# Main.net
KiCad netlist of a schematic drawn in Altium Designer
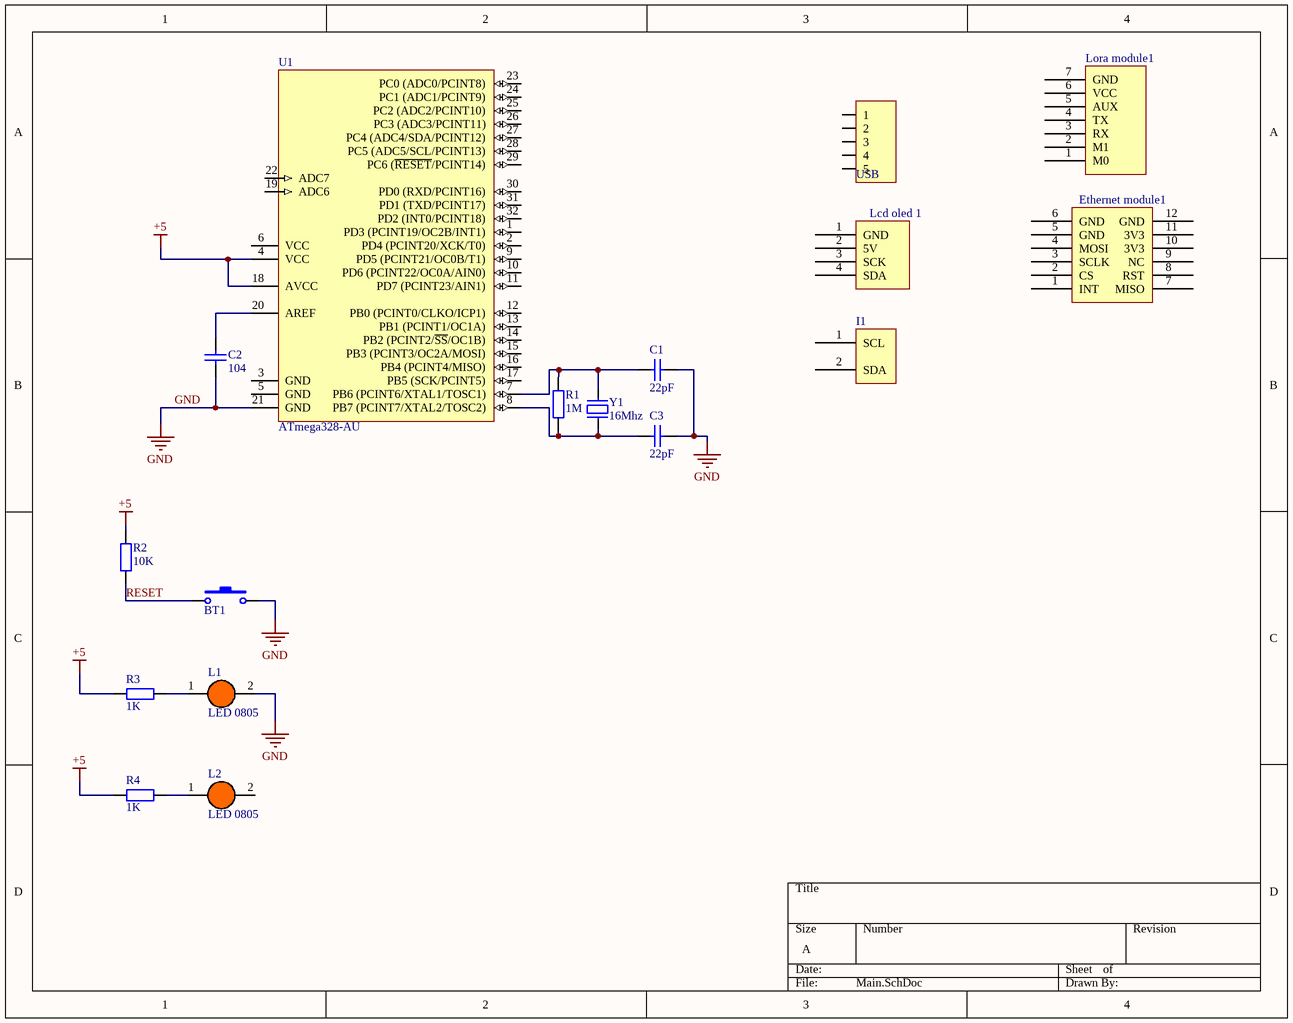
[diagram p0: Main.SchDoc]

(export (version "E")
  (design (tool "Eeschema 10.0.6"))
  (components
    (comp (ref "BT1")
      (value "Nut Nhan 2 Chan SMD 3x6x2.5")
      (footprint "Nut Nhan 2 Chan SMD 3x6x2.5")
      (libsource (lib "Altium_Lib_by_KhueNguyenCreator") (part "Nut Nhan 2 Chan SMD 3x6x2.5"))
    )
    (comp (ref "C1")
      (value "22pF")
      (footprint "tu 0603")
      (description "Dán")
      (libsource (lib "Altium_Lib_by_KhueNguyenCreator") (part "Tu 0603 22pF 50V 10%"))
    )
    (comp (ref "C2")
      (value "104")
      (footprint "tu 0603")
      (description "Dán")
      (libsource (lib "Altium_Lib_by_KhueNguyenCreator") (part "Tu 0603 104 50V 10%"))
    )
    (comp (ref "C3")
      (value "22pF")
      (footprint "tu 0603")
      (description "Dán")
      (libsource (lib "Altium_Lib_by_KhueNguyenCreator") (part "Tu 0603 22pF 50V 10%"))
    )
    (comp (ref "Ethernet module1")
      (value "Ethernet module")
      (footprint "Ethernet module - duplicate")
      (libsource (lib "SPI") (part "Ethernet module"))
    )
    (comp (ref "I1") (value "I2C") (footprint "CON2") (libsource (lib "Schlib2") (part "I2C")))
    (comp (ref "JP1")
      (value "USB")
      (footprint "JP 1x5 CT")
      (description "Cắm")
      (libsource (lib "Altium_Lib_by_KhueNguyenCreator") (part "JP 1x5 2.54 Cai Thang"))
    )
    (comp (ref "L1")
      (value "LED 0805")
      (footprint "LED-0805-Orange")
      (description "Dán")
      (libsource (lib "Altium_Lib_by_KhueNguyenCreator") (part "LED 0805 Cam"))
    )
    (comp (ref "L2")
      (value "LED 0805")
      (footprint "LED-0805-Orange")
      (description "Dán")
      (libsource (lib "Altium_Lib_by_KhueNguyenCreator") (part "LED 0805 Cam"))
    )
    (comp (ref "Lcd oled 1")
      (value "Lcd oled 1306 module")
      (footprint "LCD 1306 - duplicate")
      (libsource (lib "SPI") (part "Lcd oled 1306 module"))
    )
    (comp (ref "Lora module1")
      (value "Lora module")
      (footprint "LORA")
      (libsource (lib "SPI") (part "Lora module"))
    )
    (comp (ref "R1")
      (value "1M")
      (footprint "tro smd 0805")
      (description "Dán")
      (libsource (lib "Altium_Lib_by_KhueNguyenCreator") (part "Tro 0805 5% 1M"))
    )
    (comp (ref "R2")
      (value "10K")
      (footprint "tro smd 0603")
      (description "Dán")
      (libsource (lib "Altium_Lib_by_KhueNguyenCreator") (part "Tro 0603 5% 220R"))
    )
    (comp (ref "R3")
      (value "1K")
      (footprint "tro smd 0603")
      (description "Dán")
      (libsource (lib "Altium_Lib_by_KhueNguyenCreator") (part "Tro 0603 5% 220R"))
    )
    (comp (ref "R4")
      (value "1K")
      (footprint "tro smd 0603")
      (description "Dán")
      (libsource (lib "Altium_Lib_by_KhueNguyenCreator") (part "Tro 0603 5% 220R"))
    )
    (comp (ref "U1")
      (value "ATmega328-AU")
      (footprint "TQFP32")
      (fields (field (name "PUBLISHER") "Altium Limited"))
      (libsource (lib "LIBRARY1") (part "ATmega328-AU"))
    )
    (comp (ref "Y1")
      (value "16Mhz")
      (footprint "Thach Anh 2 chan SMD")
      (description "Crystal For all Crystal 2pin.")
      (libsource (lib "Altium_Lib_by_KhueNguyenCreator") (part "Thach Anh 2 chan SMD"))
    )
  )
  (nets
    (net (code "1") (name "+5") (class "Default")
      (node (ref "R2") (pin "2") (pinfunction "2_2") (pintype "passive"))
      (node (ref "R3") (pin "1") (pinfunction "1_1") (pintype "passive"))
      (node (ref "R4") (pin "1") (pinfunction "1_1") (pintype "passive"))
      (node (ref "U1") (pin "18") (pinfunction "AVCC_18") (pintype "power_in"))
      (node (ref "U1") (pin "4") (pinfunction "VCC_4") (pintype "power_in"))
    )
    (net (code "2") (name "/RESET") (class "Default")
      (node (ref "BT1") (pin "1") (pinfunction "1_1") (pintype "passive"))
      (node (ref "R2") (pin "1") (pinfunction "1_1") (pintype "passive"))
    )
    (net (code "3") (name "GND") (class "Default")
      (node (ref "BT1") (pin "2") (pinfunction "2_2") (pintype "passive"))
      (node (ref "C1") (pin "2") (pinfunction "2_2") (pintype "passive"))
      (node (ref "C2") (pin "2") (pinfunction "2_2") (pintype "passive"))
      (node (ref "C3") (pin "2") (pinfunction "2_2") (pintype "passive"))
      (node (ref "L1") (pin "2") (pinfunction "K_2") (pintype "passive"))
      (node (ref "U1") (pin "21") (pinfunction "GND_21") (pintype "power_in"))
    )
    (net (code "4") (name "Net-(L1-A)") (class "Default")
      (node (ref "L1") (pin "1") (pinfunction "A_1") (pintype "passive"))
      (node (ref "R3") (pin "2") (pinfunction "2_2") (pintype "passive"))
    )
    (net (code "5") (name "Net-(L2-A)") (class "Default")
      (node (ref "L2") (pin "1") (pinfunction "A_1") (pintype "passive"))
      (node (ref "R4") (pin "2") (pinfunction "2_2") (pintype "passive"))
    )
    (net (code "6") (name "Net-(U1-AREF)") (class "Default")
      (node (ref "C2") (pin "1") (pinfunction "1_1") (pintype "passive"))
      (node (ref "U1") (pin "20") (pinfunction "AREF_20") (pintype "passive"))
    )
    (net (code "7") (name "Net-(U1-PB6_(PCINT6{slash}XTAL1{slash}TOSC1))") (class "Default")
      (node (ref "C1") (pin "1") (pinfunction "1_1") (pintype "passive"))
      (node (ref "U1") (pin "7") (pinfunction "PB6_(PCINT6/XTAL1/TOSC1)_7") (pintype "bidirectional"))
      (node (ref "Y1") (pin "1") (pinfunction "1_1") (pintype "passive"))
    )
    (net (code "8") (name "Net-(U1-PB7_(PCINT7{slash}XTAL2{slash}TOSC2))") (class "Default")
      (node (ref "C3") (pin "1") (pinfunction "1_1") (pintype "passive"))
      (node (ref "R1") (pin "2") (pinfunction "2_2") (pintype "passive"))
      (node (ref "U1") (pin "8") (pinfunction "PB7_(PCINT7/XTAL2/TOSC2)_8") (pintype "bidirectional"))
      (node (ref "Y1") (pin "2") (pinfunction "2_2") (pintype "passive"))
    )
    (net (code "9") (name "unconnected-(Ethernet module1-3V3-Pad10)") (class "Default")
      (node (ref "Ethernet module1") (pin "10") (pinfunction "3V3_10") (pintype "passive"))
    )
    (net (code "10") (name "unconnected-(Ethernet module1-3V3-Pad11)") (class "Default")
      (node (ref "Ethernet module1") (pin "11") (pinfunction "3V3_11") (pintype "passive"))
    )
    (net (code "11") (name "unconnected-(Ethernet module1-CS-Pad2)") (class "Default")
      (node (ref "Ethernet module1") (pin "2") (pinfunction "CS_2") (pintype "passive"))
    )
    (net (code "12") (name "unconnected-(Ethernet module1-GND-Pad5)") (class "Default")
      (node (ref "Ethernet module1") (pin "5") (pinfunction "GND_5") (pintype "passive"))
    )
    (net (code "13") (name "unconnected-(Ethernet module1-GND-Pad6)") (class "Default")
      (node (ref "Ethernet module1") (pin "6") (pinfunction "GND_6") (pintype "passive"))
    )
    (net (code "14") (name "unconnected-(Ethernet module1-GND-Pad12)") (class "Default")
      (node (ref "Ethernet module1") (pin "12") (pinfunction "GND_12") (pintype "passive"))
    )
    (net (code "15") (name "unconnected-(Ethernet module1-INT-Pad1)") (class "Default")
      (node (ref "Ethernet module1") (pin "1") (pinfunction "INT_1") (pintype "passive"))
    )
    (net (code "16") (name "unconnected-(Ethernet module1-MISO-Pad7)") (class "Default")
      (node (ref "Ethernet module1") (pin "7") (pinfunction "MISO_7") (pintype "passive"))
    )
    (net (code "17") (name "unconnected-(Ethernet module1-MOSI-Pad4)") (class "Default")
      (node (ref "Ethernet module1") (pin "4") (pinfunction "MOSI_4") (pintype "passive"))
    )
    (net (code "18") (name "unconnected-(Ethernet module1-NC-Pad9)") (class "Default")
      (node (ref "Ethernet module1") (pin "9") (pinfunction "NC_9") (pintype "passive"))
    )
    (net (code "19") (name "unconnected-(Ethernet module1-RST-Pad8)") (class "Default")
      (node (ref "Ethernet module1") (pin "8") (pinfunction "RST_8") (pintype "passive"))
    )
    (net (code "20") (name "unconnected-(Ethernet module1-SCLK-Pad3)") (class "Default")
      (node (ref "Ethernet module1") (pin "3") (pinfunction "SCLK_3") (pintype "passive"))
    )
    (net (code "21") (name "unconnected-(I1-SCL-Pad1)") (class "Default")
      (node (ref "I1") (pin "1") (pinfunction "SCL_1") (pintype "passive"))
    )
    (net (code "22") (name "unconnected-(I1-SDA-Pad2)") (class "Default")
      (node (ref "I1") (pin "2") (pinfunction "SDA_2") (pintype "passive"))
    )
    (net (code "23") (name "unconnected-(JP1-Pad1)") (class "Default")
      (node (ref "JP1") (pin "1") (pinfunction "1_1") (pintype "passive"))
    )
    (net (code "24") (name "unconnected-(JP1-Pad2)") (class "Default")
      (node (ref "JP1") (pin "2") (pinfunction "2_2") (pintype "passive"))
    )
    (net (code "25") (name "unconnected-(JP1-Pad3)") (class "Default")
      (node (ref "JP1") (pin "3") (pinfunction "3_3") (pintype "passive"))
    )
    (net (code "26") (name "unconnected-(JP1-Pad4)") (class "Default")
      (node (ref "JP1") (pin "4") (pinfunction "4_4") (pintype "passive"))
    )
    (net (code "27") (name "unconnected-(JP1-Pad5)") (class "Default")
      (node (ref "JP1") (pin "5") (pinfunction "5_5") (pintype "passive"))
    )
    (net (code "28") (name "unconnected-(L2-K-Pad2)") (class "Default")
      (node (ref "L2") (pin "2") (pinfunction "K_2") (pintype "passive"))
    )
    (net (code "29") (name "unconnected-(Lcd oled 1-5V-Pad2)") (class "Default")
      (node (ref "Lcd oled 1") (pin "2") (pinfunction "5V_2") (pintype "passive"))
    )
    (net (code "30") (name "unconnected-(Lcd oled 1-GND-Pad1)") (class "Default")
      (node (ref "Lcd oled 1") (pin "1") (pinfunction "GND_1") (pintype "passive"))
    )
    (net (code "31") (name "unconnected-(Lcd oled 1-SCK-Pad3)") (class "Default")
      (node (ref "Lcd oled 1") (pin "3") (pinfunction "SCK_3") (pintype "passive"))
    )
    (net (code "32") (name "unconnected-(Lcd oled 1-SDA-Pad4)") (class "Default")
      (node (ref "Lcd oled 1") (pin "4") (pinfunction "SDA_4") (pintype "passive"))
    )
    (net (code "33") (name "unconnected-(Lora module1-AUX-Pad5)") (class "Default")
      (node (ref "Lora module1") (pin "5") (pinfunction "AUX_5") (pintype "passive"))
    )
    (net (code "34") (name "unconnected-(Lora module1-GND-Pad7)") (class "Default")
      (node (ref "Lora module1") (pin "7") (pinfunction "GND_7") (pintype "power_in"))
    )
    (net (code "35") (name "unconnected-(Lora module1-M0-Pad1)") (class "Default")
      (node (ref "Lora module1") (pin "1") (pinfunction "M0_1") (pintype "passive"))
    )
    (net (code "36") (name "unconnected-(Lora module1-M1-Pad2)") (class "Default")
      (node (ref "Lora module1") (pin "2") (pinfunction "M1_2") (pintype "passive"))
    )
    (net (code "37") (name "unconnected-(Lora module1-RX-Pad3)") (class "Default")
      (node (ref "Lora module1") (pin "3") (pinfunction "RX_3") (pintype "passive"))
    )
    (net (code "38") (name "unconnected-(Lora module1-TX-Pad4)") (class "Default")
      (node (ref "Lora module1") (pin "4") (pinfunction "TX_4") (pintype "passive"))
    )
    (net (code "39") (name "unconnected-(Lora module1-VCC-Pad6)") (class "Default")
      (node (ref "Lora module1") (pin "6") (pinfunction "VCC_6") (pintype "power_in"))
    )
    (net (code "40") (name "unconnected-(R1-Pad1)") (class "Default")
      (node (ref "R1") (pin "1") (pinfunction "1_1") (pintype "passive"))
    )
    (net (code "41") (name "unconnected-(U1-ADC6-Pad19)") (class "Default")
      (node (ref "U1") (pin "19") (pinfunction "ADC6_19") (pintype "input"))
    )
    (net (code "42") (name "unconnected-(U1-ADC7-Pad22)") (class "Default")
      (node (ref "U1") (pin "22") (pinfunction "ADC7_22") (pintype "input"))
    )
    (net (code "43") (name "unconnected-(U1-GND-Pad3)") (class "Default")
      (node (ref "U1") (pin "3") (pinfunction "GND_3") (pintype "power_in"))
    )
    (net (code "44") (name "unconnected-(U1-GND-Pad5)") (class "Default")
      (node (ref "U1") (pin "5") (pinfunction "GND_5") (pintype "power_in"))
    )
    (net (code "45") (name "unconnected-(U1-PB0_(PCINT0{slash}CLKO{slash}ICP1)-Pad12)") (class "Default")
      (node (ref "U1") (pin "12") (pinfunction "PB0_(PCINT0/CLKO/ICP1)_12") (pintype "bidirectional"))
    )
    (net (code "46") (name "unconnected-(U1-PB1_(PCINT1{slash}OC1A)-Pad13)") (class "Default")
      (node (ref "U1") (pin "13") (pinfunction "PB1_(PCINT1/OC1A)_13") (pintype "bidirectional"))
    )
    (net (code "47") (name "unconnected-(U1-PB2_(PCINT2{slash}~{SS}{slash}OC1B)-Pad14)") (class "Default")
      (node (ref "U1") (pin "14") (pinfunction "PB2_(PCINT2/~{SS}/OC1B)_14") (pintype "bidirectional"))
    )
    (net (code "48") (name "unconnected-(U1-PB3_(PCINT3{slash}OC2A{slash}MOSI)-Pad15)") (class "Default")
      (node (ref "U1") (pin "15") (pinfunction "PB3_(PCINT3/OC2A/MOSI)_15") (pintype "bidirectional"))
    )
    (net (code "49") (name "unconnected-(U1-PB4_(PCINT4{slash}MISO)-Pad16)") (class "Default")
      (node (ref "U1") (pin "16") (pinfunction "PB4_(PCINT4/MISO)_16") (pintype "bidirectional"))
    )
    (net (code "50") (name "unconnected-(U1-PB5_(SCK{slash}PCINT5)-Pad17)") (class "Default")
      (node (ref "U1") (pin "17") (pinfunction "PB5_(SCK/PCINT5)_17") (pintype "bidirectional"))
    )
    (net (code "51") (name "unconnected-(U1-PC0_(ADC0{slash}PCINT8)-Pad23)") (class "Default")
      (node (ref "U1") (pin "23") (pinfunction "PC0_(ADC0/PCINT8)_23") (pintype "bidirectional"))
    )
    (net (code "52") (name "unconnected-(U1-PC1_(ADC1{slash}PCINT9)-Pad24)") (class "Default")
      (node (ref "U1") (pin "24") (pinfunction "PC1_(ADC1/PCINT9)_24") (pintype "bidirectional"))
    )
    (net (code "53") (name "unconnected-(U1-PC2_(ADC2{slash}PCINT10)-Pad25)") (class "Default")
      (node (ref "U1") (pin "25") (pinfunction "PC2_(ADC2/PCINT10)_25") (pintype "bidirectional"))
    )
    (net (code "54") (name "unconnected-(U1-PC3_(ADC3{slash}PCINT11)-Pad26)") (class "Default")
      (node (ref "U1") (pin "26") (pinfunction "PC3_(ADC3/PCINT11)_26") (pintype "bidirectional"))
    )
    (net (code "55") (name "unconnected-(U1-PC4_(ADC4{slash}SDA{slash}PCINT12)-Pad27)") (class "Default")
      (node (ref "U1") (pin "27") (pinfunction "PC4_(ADC4/SDA/PCINT12)_27") (pintype "bidirectional"))
    )
    (net (code "56") (name "unconnected-(U1-PC5_(ADC5{slash}SCL{slash}PCINT13)-Pad28)") (class "Default")
      (node (ref "U1") (pin "28") (pinfunction "PC5_(ADC5/SCL/PCINT13)_28") (pintype "bidirectional"))
    )
    (net (code "57") (name "unconnected-(U1-PC6_(~{RESET}{slash}PCINT14)-Pad29)") (class "Default")
      (node (ref "U1") (pin "29") (pinfunction "PC6_(~{RESET}/PCINT14)_29") (pintype "bidirectional"))
    )
    (net (code "58") (name "unconnected-(U1-PD0_(RXD{slash}PCINT16)-Pad30)") (class "Default")
      (node (ref "U1") (pin "30") (pinfunction "PD0_(RXD/PCINT16)_30") (pintype "bidirectional"))
    )
    (net (code "59") (name "unconnected-(U1-PD1_(TXD{slash}PCINT17)-Pad31)") (class "Default")
      (node (ref "U1") (pin "31") (pinfunction "PD1_(TXD/PCINT17)_31") (pintype "bidirectional"))
    )
    (net (code "60") (name "unconnected-(U1-PD2_(INT0{slash}PCINT18)-Pad32)") (class "Default")
      (node (ref "U1") (pin "32") (pinfunction "PD2_(INT0/PCINT18)_32") (pintype "bidirectional"))
    )
    (net (code "61") (name "unconnected-(U1-PD3_(PCINT19{slash}OC2B{slash}INT1)-Pad1)") (class "Default")
      (node (ref "U1") (pin "1") (pinfunction "PD3_(PCINT19/OC2B/INT1)_1") (pintype "bidirectional"))
    )
    (net (code "62") (name "unconnected-(U1-PD4_(PCINT20{slash}XCK{slash}T0)-Pad2)") (class "Default")
      (node (ref "U1") (pin "2") (pinfunction "PD4_(PCINT20/XCK/T0)_2") (pintype "bidirectional"))
    )
    (net (code "63") (name "unconnected-(U1-PD5_(PCINT21{slash}OC0B{slash}T1)-Pad9)") (class "Default")
      (node (ref "U1") (pin "9") (pinfunction "PD5_(PCINT21/OC0B/T1)_9") (pintype "bidirectional"))
    )
    (net (code "64") (name "unconnected-(U1-PD6_(PCINT22{slash}OC0A{slash}AIN0)-Pad10)") (class "Default")
      (node (ref "U1") (pin "10") (pinfunction "PD6_(PCINT22/OC0A/AIN0)_10") (pintype "bidirectional"))
    )
    (net (code "65") (name "unconnected-(U1-PD7_(PCINT23{slash}AIN1)-Pad11)") (class "Default")
      (node (ref "U1") (pin "11") (pinfunction "PD7_(PCINT23/AIN1)_11") (pintype "bidirectional"))
    )
    (net (code "66") (name "unconnected-(U1-VCC-Pad6)") (class "Default")
      (node (ref "U1") (pin "6") (pinfunction "VCC_6") (pintype "power_in"))
    )
  )
)
